# OpenPLC.net
KiCad netlist of a schematic drawn in EAGLE
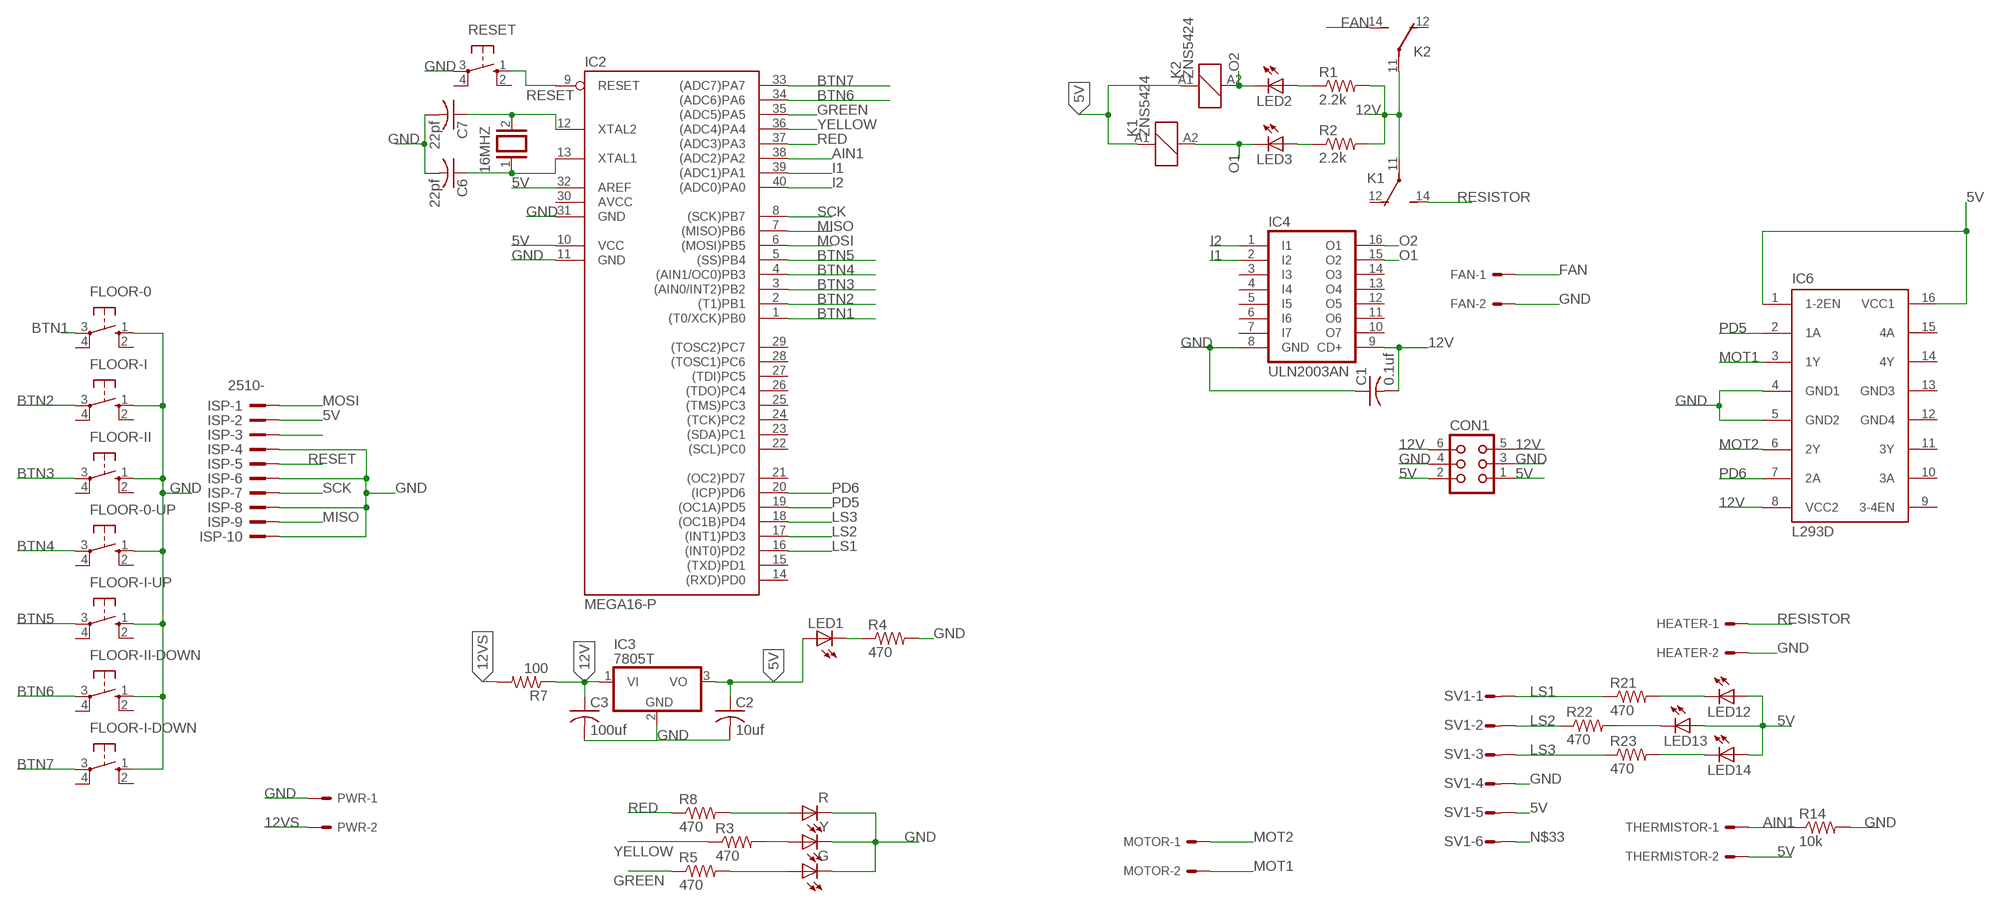
[diagram p0: schematic, sheet 1]

(export (version "E")
  (design (tool "Eeschema 10.0.6"))
  (components
    (comp (ref "16MHZ")
      (value "XTAL/S")
      (footprint "eagle-import:QS")
      (libsource (lib "eagle-import") (part "XTAL/S"))
    )
    (comp (ref "C1")
      (value "0.1uf")
      (footprint "eagle-import:C0805")
      (libsource (lib "eagle-import") (part "C-USC0805"))
    )
    (comp (ref "C2")
      (value "10uf")
      (footprint "eagle-import:C025-025X050")
      (libsource (lib "eagle-import") (part "C-US025-025X050"))
    )
    (comp (ref "C3")
      (value "100uf")
      (footprint "eagle-import:C025-025X050")
      (libsource (lib "eagle-import") (part "C-US025-025X050"))
    )
    (comp (ref "C6")
      (value "22pf")
      (footprint "eagle-import:C0805")
      (libsource (lib "eagle-import") (part "C-USC0805"))
    )
    (comp (ref "C7")
      (value "22pf")
      (footprint "eagle-import:C0805")
      (libsource (lib "eagle-import") (part "C-USC0805"))
    )
    (comp (ref "CON1")
      (value "CON06")
      (footprint "eagle-import:CON06")
      (libsource (lib "eagle-import") (part "CON06"))
    )
    (comp (ref "FAN")
      (value "KK-156-2")
      (footprint "eagle-import:KK-156-2")
      (libsource (lib "eagle-import") (part "KK-156-2"))
    )
    (comp (ref "FLOOR-0")
      (value "10-XX")
      (footprint "eagle-import:B3F-10XX")
      (fields (field (name "MPN") "B3F-1000"))
      (libsource (lib "eagle-import") (part "10-XX"))
    )
    (comp (ref "FLOOR-0-UP")
      (value "10-XX")
      (footprint "eagle-import:B3F-10XX")
      (fields (field (name "MPN") "B3F-1000"))
      (libsource (lib "eagle-import") (part "10-XX"))
    )
    (comp (ref "FLOOR-I")
      (value "10-XX")
      (footprint "eagle-import:B3F-10XX")
      (fields (field (name "MPN") "B3F-1000"))
      (libsource (lib "eagle-import") (part "10-XX"))
    )
    (comp (ref "FLOOR-I-DOWN")
      (value "10-XX")
      (footprint "eagle-import:B3F-10XX")
      (fields (field (name "MPN") "B3F-1000"))
      (libsource (lib "eagle-import") (part "10-XX"))
    )
    (comp (ref "FLOOR-I-UP")
      (value "10-XX")
      (footprint "eagle-import:B3F-10XX")
      (fields (field (name "MPN") "B3F-1000"))
      (libsource (lib "eagle-import") (part "10-XX"))
    )
    (comp (ref "FLOOR-II")
      (value "10-XX")
      (footprint "eagle-import:B3F-10XX")
      (fields (field (name "MPN") "B3F-1000"))
      (libsource (lib "eagle-import") (part "10-XX"))
    )
    (comp (ref "FLOOR-II-DOWN")
      (value "10-XX")
      (footprint "eagle-import:B3F-10XX")
      (fields (field (name "MPN") "B3F-1000"))
      (libsource (lib "eagle-import") (part "10-XX"))
    )
    (comp (ref "G")
      (value "LED10MM")
      (footprint "eagle-import:LED10MM")
      (libsource (lib "eagle-import") (part "LED10MM"))
    )
    (comp (ref "HEATER")
      (value "KK-156-2")
      (footprint "eagle-import:KK-156-2")
      (libsource (lib "eagle-import") (part "KK-156-2"))
    )
    (comp (ref "IC2")
      (value "MEGA16-P")
      (footprint "eagle-import:DIL40")
      (fields (field (name "MPN") "ATMEGA16-16PU"))
      (libsource (lib "eagle-import") (part "MEGA16-P"))
    )
    (comp (ref "IC3")
      (value "7805T")
      (footprint "eagle-import:TO220H")
      (libsource (lib "eagle-import") (part "78T05"))
    )
    (comp (ref "IC4")
      (value "ULN2003AN")
      (footprint "eagle-import:DIL16")
      (libsource (lib "eagle-import") (part "ULN2003AN"))
    )
    (comp (ref "IC6")
      (value "L293D")
      (footprint "eagle-import:DIL16")
      (libsource (lib "eagle-import") (part "L293D"))
    )
    (comp (ref "ISP")
      (value "2510-")
      (footprint "eagle-import:PAK100_2500-10")
      (fields (field (name "MF") "3M") (field (name "MPN") "2510-6002UB"))
      (libsource (lib "eagle-import") (part "2510-"))
    )
    (comp (ref "K1")
      (value "ZNS5424")
      (footprint "eagle-import:ZN5")
      (libsource (lib "eagle-import") (part "ZNS5424"))
    )
    (comp (ref "K2")
      (value "ZNS5424")
      (footprint "eagle-import:ZN5")
      (libsource (lib "eagle-import") (part "ZNS5424"))
    )
    (comp (ref "LED1")
      (value "LEDSML0805")
      (footprint "eagle-import:SML0805")
      (libsource (lib "eagle-import") (part "LEDSML0805"))
    )
    (comp (ref "LED2")
      (value "LEDSML0805")
      (footprint "eagle-import:SML0805")
      (libsource (lib "eagle-import") (part "LEDSML0805"))
    )
    (comp (ref "LED3")
      (value "LEDSML0805")
      (footprint "eagle-import:SML0805")
      (libsource (lib "eagle-import") (part "LEDSML0805"))
    )
    (comp (ref "LED12")
      (value "LEDSML0805")
      (footprint "eagle-import:SML0805")
      (libsource (lib "eagle-import") (part "LEDSML0805"))
    )
    (comp (ref "LED13")
      (value "LEDSML0805")
      (footprint "eagle-import:SML0805")
      (libsource (lib "eagle-import") (part "LEDSML0805"))
    )
    (comp (ref "LED14")
      (value "LEDSML0805")
      (footprint "eagle-import:SML0805")
      (libsource (lib "eagle-import") (part "LEDSML0805"))
    )
    (comp (ref "MOTOR")
      (value "KK-156-2")
      (footprint "eagle-import:KK-156-2")
      (libsource (lib "eagle-import") (part "KK-156-2"))
    )
    (comp (ref "PWR")
      (value "KK-156-2")
      (footprint "eagle-import:KK-156-2")
      (libsource (lib "eagle-import") (part "KK-156-2"))
    )
    (comp (ref "R")
      (value "LED10MM")
      (footprint "eagle-import:LED10MM")
      (libsource (lib "eagle-import") (part "LED10MM"))
    )
    (comp (ref "R1")
      (value "2.2k")
      (footprint "eagle-import:R0805")
      (libsource (lib "eagle-import") (part "R-US_R0805"))
    )
    (comp (ref "R2")
      (value "2.2k")
      (footprint "eagle-import:R0805")
      (libsource (lib "eagle-import") (part "R-US_R0805"))
    )
    (comp (ref "R3")
      (value "470")
      (footprint "eagle-import:R0805")
      (libsource (lib "eagle-import") (part "R-US_R0805"))
    )
    (comp (ref "R4")
      (value "470")
      (footprint "eagle-import:R0805")
      (libsource (lib "eagle-import") (part "R-US_R0805"))
    )
    (comp (ref "R5")
      (value "470")
      (footprint "eagle-import:R0805")
      (libsource (lib "eagle-import") (part "R-US_R0805"))
    )
    (comp (ref "R7")
      (value "100")
      (footprint "eagle-import:0207_12")
      (libsource (lib "eagle-import") (part "R-US_0207/12"))
    )
    (comp (ref "R8")
      (value "470")
      (footprint "eagle-import:R0805")
      (libsource (lib "eagle-import") (part "R-US_R0805"))
    )
    (comp (ref "R14")
      (value "10k")
      (footprint "eagle-import:R0805")
      (libsource (lib "eagle-import") (part "R-US_R0805"))
    )
    (comp (ref "R21")
      (value "470")
      (footprint "eagle-import:R0805")
      (libsource (lib "eagle-import") (part "R-US_R0805"))
    )
    (comp (ref "R22")
      (value "470")
      (footprint "eagle-import:R0805")
      (libsource (lib "eagle-import") (part "R-US_R0805"))
    )
    (comp (ref "R23")
      (value "470")
      (footprint "eagle-import:R0805")
      (libsource (lib "eagle-import") (part "R-US_R0805"))
    )
    (comp (ref "RESET")
      (value "10-XX")
      (footprint "eagle-import:B3F-10XX")
      (fields (field (name "MPN") "B3F-1000"))
      (libsource (lib "eagle-import") (part "10-XX"))
    )
    (comp (ref "SV1")
      (value "L06P")
      (footprint "eagle-import:L06P")
      (libsource (lib "eagle-import") (part "L06P"))
    )
    (comp (ref "THERMISTOR")
      (value "KK-156-2")
      (footprint "eagle-import:KK-156-2")
      (libsource (lib "eagle-import") (part "KK-156-2"))
    )
    (comp (ref "Y")
      (value "LED10MM")
      (footprint "eagle-import:LED10MM")
      (libsource (lib "eagle-import") (part "LED10MM"))
    )
  )
  (nets
    (net (code "1") (name "/AIN1") (class "Default")
      (node (ref "IC2") (pin "38") (pinfunction "(ADC2)PA2_38") (pintype "bidirectional"))
      (node (ref "R14") (pin "1") (pinfunction "1_1") (pintype "passive"))
      (node (ref "THERMISTOR") (pin "1") (pinfunction "S_1") (pintype "passive"))
    )
    (net (code "2") (name "/AVCC") (class "Default")
      (node (ref "IC2") (pin "30") (pinfunction "AVCC_30") (pintype "power_in"))
    )
    (net (code "3") (name "/BTN1") (class "Default")
      (node (ref "FLOOR-0") (pin "3") (pinfunction "P_3") (pintype "passive"))
      (node (ref "IC2") (pin "1") (pinfunction "(T0/XCK)PB0_1") (pintype "bidirectional"))
    )
    (net (code "4") (name "/BTN2") (class "Default")
      (node (ref "FLOOR-I") (pin "3") (pinfunction "P_3") (pintype "passive"))
      (node (ref "IC2") (pin "2") (pinfunction "(T1)PB1_2") (pintype "bidirectional"))
    )
    (net (code "5") (name "/BTN3") (class "Default")
      (node (ref "FLOOR-II") (pin "3") (pinfunction "P_3") (pintype "passive"))
      (node (ref "IC2") (pin "3") (pinfunction "(AIN0/INT2)PB2_3") (pintype "bidirectional"))
    )
    (net (code "6") (name "/BTN4") (class "Default")
      (node (ref "FLOOR-0-UP") (pin "3") (pinfunction "P_3") (pintype "passive"))
      (node (ref "IC2") (pin "4") (pinfunction "(AIN1/OC0)PB3_4") (pintype "bidirectional"))
    )
    (net (code "7") (name "/BTN5") (class "Default")
      (node (ref "FLOOR-I-UP") (pin "3") (pinfunction "P_3") (pintype "passive"))
      (node (ref "IC2") (pin "5") (pinfunction "(SS)PB4_5") (pintype "bidirectional"))
    )
    (net (code "8") (name "/BTN6") (class "Default")
      (node (ref "FLOOR-II-DOWN") (pin "3") (pinfunction "P_3") (pintype "passive"))
      (node (ref "IC2") (pin "34") (pinfunction "(ADC6)PA6_34") (pintype "bidirectional"))
    )
    (net (code "9") (name "/BTN7") (class "Default")
      (node (ref "FLOOR-I-DOWN") (pin "3") (pinfunction "P_3") (pintype "passive"))
      (node (ref "IC2") (pin "33") (pinfunction "(ADC7)PA7_33") (pintype "bidirectional"))
    )
    (net (code "10") (name "/FAN") (class "Default")
      (node (ref "FAN") (pin "1") (pinfunction "S_1") (pintype "passive"))
      (node (ref "K2") (pin "14") (pinfunction "S_14") (pintype "passive"))
    )
    (net (code "11") (name "/GND") (class "Default")
      (node (ref "C1") (pin "1") (pinfunction "1_1") (pintype "passive"))
      (node (ref "C2") (pin "2") (pinfunction "2_2") (pintype "passive"))
      (node (ref "C3") (pin "2") (pinfunction "2_2") (pintype "passive"))
      (node (ref "C6") (pin "2") (pinfunction "2_2") (pintype "passive"))
      (node (ref "C7") (pin "2") (pinfunction "2_2") (pintype "passive"))
      (node (ref "CON1") (pin "3") (pinfunction "3_3") (pintype "passive"))
      (node (ref "CON1") (pin "4") (pinfunction "4_4") (pintype "passive"))
      (node (ref "FAN") (pin "2") (pinfunction "S_2") (pintype "passive"))
      (node (ref "FLOOR-0") (pin "1") (pinfunction "S_1") (pintype "passive"))
      (node (ref "FLOOR-0-UP") (pin "1") (pinfunction "S_1") (pintype "passive"))
      (node (ref "FLOOR-I") (pin "1") (pinfunction "S_1") (pintype "passive"))
      (node (ref "FLOOR-I-DOWN") (pin "1") (pinfunction "S_1") (pintype "passive"))
      (node (ref "FLOOR-I-UP") (pin "1") (pinfunction "S_1") (pintype "passive"))
      (node (ref "FLOOR-II") (pin "1") (pinfunction "S_1") (pintype "passive"))
      (node (ref "FLOOR-II-DOWN") (pin "1") (pinfunction "S_1") (pintype "passive"))
      (node (ref "G") (pin "K") (pinfunction "C_K") (pintype "passive"))
      (node (ref "HEATER") (pin "2") (pinfunction "S_2") (pintype "passive"))
      (node (ref "IC2") (pin "11") (pinfunction "GND_11") (pintype "power_in"))
      (node (ref "IC2") (pin "31") (pinfunction "GND_31") (pintype "power_in"))
      (node (ref "IC3") (pin "2") (pinfunction "GND_2") (pintype "passive"))
      (node (ref "IC4") (pin "8") (pinfunction "GND_8") (pintype "power_in"))
      (node (ref "IC6") (pin "4") (pinfunction "GND1_4") (pintype "power_in"))
      (node (ref "IC6") (pin "5") (pinfunction "GND2_5") (pintype "power_in"))
      (node (ref "ISP") (pin "10") (pinfunction "KL_10") (pintype "passive"))
      (node (ref "ISP") (pin "4") (pinfunction "KL_4") (pintype "passive"))
      (node (ref "ISP") (pin "6") (pinfunction "KL_6") (pintype "passive"))
      (node (ref "ISP") (pin "8") (pinfunction "KL_8") (pintype "passive"))
      (node (ref "PWR") (pin "1") (pinfunction "S_1") (pintype "passive"))
      (node (ref "R") (pin "K") (pinfunction "C_K") (pintype "passive"))
      (node (ref "R14") (pin "2") (pinfunction "2_2") (pintype "passive"))
      (node (ref "R4") (pin "2") (pinfunction "2_2") (pintype "passive"))
      (node (ref "RESET") (pin "3") (pinfunction "P_3") (pintype "passive"))
      (node (ref "SV1") (pin "4") (pinfunction "S_4") (pintype "passive"))
      (node (ref "Y") (pin "K") (pinfunction "C_K") (pintype "passive"))
    )
    (net (code "12") (name "/GND3") (class "Default")
      (node (ref "IC6") (pin "13") (pinfunction "GND3_13") (pintype "power_in"))
    )
    (net (code "13") (name "/GND4") (class "Default")
      (node (ref "IC6") (pin "12") (pinfunction "GND4_12") (pintype "power_in"))
    )
    (net (code "14") (name "/GREEN") (class "Default")
      (node (ref "IC2") (pin "35") (pinfunction "(ADC5)PA5_35") (pintype "bidirectional"))
      (node (ref "R5") (pin "1") (pinfunction "1_1") (pintype "passive"))
    )
    (net (code "15") (name "/I1") (class "Default")
      (node (ref "IC2") (pin "39") (pinfunction "(ADC1)PA1_39") (pintype "bidirectional"))
      (node (ref "IC4") (pin "2") (pinfunction "I2_2") (pintype "input"))
    )
    (net (code "16") (name "/I2") (class "Default")
      (node (ref "IC2") (pin "40") (pinfunction "(ADC0)PA0_40") (pintype "bidirectional"))
      (node (ref "IC4") (pin "1") (pinfunction "I1_1") (pintype "input"))
    )
    (net (code "17") (name "/LS1") (class "Default")
      (node (ref "IC2") (pin "16") (pinfunction "(INT0)PD2_16") (pintype "bidirectional"))
      (node (ref "R21") (pin "1") (pinfunction "1_1") (pintype "passive"))
      (node (ref "SV1") (pin "1") (pinfunction "S_1") (pintype "passive"))
    )
    (net (code "18") (name "/LS2") (class "Default")
      (node (ref "IC2") (pin "17") (pinfunction "(INT1)PD3_17") (pintype "bidirectional"))
      (node (ref "R22") (pin "1") (pinfunction "1_1") (pintype "passive"))
      (node (ref "SV1") (pin "2") (pinfunction "S_2") (pintype "passive"))
    )
    (net (code "19") (name "/LS3") (class "Default")
      (node (ref "IC2") (pin "18") (pinfunction "(OC1B)PD4_18") (pintype "bidirectional"))
      (node (ref "R23") (pin "1") (pinfunction "1_1") (pintype "passive"))
      (node (ref "SV1") (pin "3") (pinfunction "S_3") (pintype "passive"))
    )
    (net (code "20") (name "/MISO") (class "Default")
      (node (ref "IC2") (pin "7") (pinfunction "(MISO)PB6_7") (pintype "bidirectional"))
      (node (ref "ISP") (pin "9") (pinfunction "KL_9") (pintype "passive"))
    )
    (net (code "21") (name "/MOSI") (class "Default")
      (node (ref "IC2") (pin "6") (pinfunction "(MOSI)PB5_6") (pintype "bidirectional"))
      (node (ref "ISP") (pin "1") (pinfunction "KL_1") (pintype "passive"))
    )
    (net (code "22") (name "/MOT1") (class "Default")
      (node (ref "IC6") (pin "3") (pinfunction "1Y_3") (pintype "output"))
      (node (ref "MOTOR") (pin "2") (pinfunction "S_2") (pintype "passive"))
    )
    (net (code "23") (name "/MOT2") (class "Default")
      (node (ref "IC6") (pin "6") (pinfunction "2Y_6") (pintype "output"))
      (node (ref "MOTOR") (pin "1") (pinfunction "S_1") (pintype "passive"))
    )
    (net (code "24") (name "/N$33") (class "Default")
      (node (ref "SV1") (pin "6") (pinfunction "S_6") (pintype "passive"))
    )
    (net (code "25") (name "/O1") (class "Default")
      (node (ref "IC4") (pin "15") (pinfunction "O2_15") (pintype "open_collector"))
      (node (ref "K1") (pin "A2") (pinfunction "2_A2") (pintype "passive"))
      (node (ref "LED3") (pin "C") (pinfunction "C_C") (pintype "passive"))
    )
    (net (code "26") (name "/O2") (class "Default")
      (node (ref "IC4") (pin "16") (pinfunction "O1_16") (pintype "open_collector"))
      (node (ref "K2") (pin "A2") (pinfunction "2_A2") (pintype "passive"))
      (node (ref "LED2") (pin "C") (pinfunction "C_C") (pintype "passive"))
    )
    (net (code "27") (name "/PD5") (class "Default")
      (node (ref "IC2") (pin "19") (pinfunction "(OC1A)PD5_19") (pintype "bidirectional"))
      (node (ref "IC6") (pin "2") (pinfunction "1A_2") (pintype "input"))
    )
    (net (code "28") (name "/PD6") (class "Default")
      (node (ref "IC2") (pin "20") (pinfunction "(ICP)PD6_20") (pintype "bidirectional"))
      (node (ref "IC6") (pin "7") (pinfunction "2A_7") (pintype "input"))
    )
    (net (code "29") (name "/RED") (class "Default")
      (node (ref "IC2") (pin "37") (pinfunction "(ADC3)PA3_37") (pintype "bidirectional"))
      (node (ref "R8") (pin "1") (pinfunction "1_1") (pintype "passive"))
    )
    (net (code "30") (name "/RESET") (class "Default")
      (node (ref "IC2") (pin "9") (pinfunction "RESET_9") (pintype "input"))
      (node (ref "ISP") (pin "5") (pinfunction "KL_5") (pintype "passive"))
      (node (ref "RESET") (pin "1") (pinfunction "S_1") (pintype "passive"))
    )
    (net (code "31") (name "/RESISTOR") (class "Default")
      (node (ref "HEATER") (pin "1") (pinfunction "S_1") (pintype "passive"))
      (node (ref "K1") (pin "14") (pinfunction "S_14") (pintype "passive"))
    )
    (net (code "32") (name "/SCK") (class "Default")
      (node (ref "IC2") (pin "8") (pinfunction "(SCK)PB7_8") (pintype "bidirectional"))
      (node (ref "ISP") (pin "7") (pinfunction "KL_7") (pintype "passive"))
    )
    (net (code "33") (name "/YELLOW") (class "Default")
      (node (ref "IC2") (pin "36") (pinfunction "(ADC4)PA4_36") (pintype "bidirectional"))
      (node (ref "R3") (pin "1") (pinfunction "1_1") (pintype "passive"))
    )
    (net (code "34") (name "5V") (class "Default")
      (node (ref "C2") (pin "1") (pinfunction "1_1") (pintype "passive"))
      (node (ref "CON1") (pin "1") (pinfunction "1_1") (pintype "passive"))
      (node (ref "CON1") (pin "2") (pinfunction "2_2") (pintype "passive"))
      (node (ref "IC2") (pin "10") (pinfunction "VCC_10") (pintype "power_in"))
      (node (ref "IC2") (pin "32") (pinfunction "AREF_32") (pintype "passive"))
      (node (ref "IC3") (pin "3") (pinfunction "VO_3") (pintype "passive"))
      (node (ref "IC6") (pin "1") (pinfunction "1-2EN_1") (pintype "input"))
      (node (ref "IC6") (pin "16") (pinfunction "VCC1_16") (pintype "power_in"))
      (node (ref "ISP") (pin "2") (pinfunction "KL_2") (pintype "passive"))
      (node (ref "K1") (pin "A1") (pinfunction "1_A1") (pintype "passive"))
      (node (ref "K2") (pin "A1") (pinfunction "1_A1") (pintype "passive"))
      (node (ref "LED1") (pin "A") (pinfunction "A_A") (pintype "passive"))
      (node (ref "LED12") (pin "A") (pinfunction "A_A") (pintype "passive"))
      (node (ref "LED13") (pin "A") (pinfunction "A_A") (pintype "passive"))
      (node (ref "LED14") (pin "A") (pinfunction "A_A") (pintype "passive"))
      (node (ref "SV1") (pin "5") (pinfunction "S_5") (pintype "passive"))
      (node (ref "THERMISTOR") (pin "2") (pinfunction "S_2") (pintype "passive"))
    )
    (net (code "35") (name "12V") (class "Default")
      (node (ref "C1") (pin "2") (pinfunction "2_2") (pintype "passive"))
      (node (ref "C3") (pin "1") (pinfunction "1_1") (pintype "passive"))
      (node (ref "CON1") (pin "5") (pinfunction "5_5") (pintype "passive"))
      (node (ref "CON1") (pin "6") (pinfunction "6_6") (pintype "passive"))
      (node (ref "IC3") (pin "1") (pinfunction "VI_1") (pintype "input"))
      (node (ref "IC4") (pin "9") (pinfunction "CD+_9") (pintype "passive"))
      (node (ref "IC6") (pin "8") (pinfunction "VCC2_8") (pintype "power_in"))
      (node (ref "K1") (pin "11") (pinfunction "P_11") (pintype "passive"))
      (node (ref "K2") (pin "11") (pinfunction "P_11") (pintype "passive"))
      (node (ref "R1") (pin "2") (pinfunction "2_2") (pintype "passive"))
      (node (ref "R2") (pin "2") (pinfunction "2_2") (pintype "passive"))
      (node (ref "R7") (pin "1") (pinfunction "1_1") (pintype "passive"))
    )
    (net (code "36") (name "12VS") (class "Default")
      (node (ref "PWR") (pin "2") (pinfunction "S_2") (pintype "passive"))
      (node (ref "R7") (pin "2") (pinfunction "2_2") (pintype "passive"))
    )
    (net (code "37") (name "Net-(G-PadA)") (class "Default")
      (node (ref "G") (pin "A") (pinfunction "A_A") (pintype "passive"))
      (node (ref "R5") (pin "2") (pinfunction "2_2") (pintype "passive"))
    )
    (net (code "38") (name "Net-(IC2-XTAL1)") (class "Default")
      (node (ref "16MHZ") (pin "1") (pinfunction "1_1") (pintype "passive"))
      (node (ref "C6") (pin "1") (pinfunction "1_1") (pintype "passive"))
      (node (ref "IC2") (pin "13") (pinfunction "XTAL1_13") (pintype "bidirectional"))
    )
    (net (code "39") (name "Net-(IC2-XTAL2)") (class "Default")
      (node (ref "16MHZ") (pin "2") (pinfunction "2_2") (pintype "passive"))
      (node (ref "C7") (pin "1") (pinfunction "1_1") (pintype "passive"))
      (node (ref "IC2") (pin "12") (pinfunction "XTAL2_12") (pintype "bidirectional"))
    )
    (net (code "40") (name "Net-(LED1-PadC)") (class "Default")
      (node (ref "LED1") (pin "C") (pinfunction "C_C") (pintype "passive"))
      (node (ref "R4") (pin "1") (pinfunction "1_1") (pintype "passive"))
    )
    (net (code "41") (name "Net-(LED2-PadA)") (class "Default")
      (node (ref "LED2") (pin "A") (pinfunction "A_A") (pintype "passive"))
      (node (ref "R1") (pin "1") (pinfunction "1_1") (pintype "passive"))
    )
    (net (code "42") (name "Net-(LED3-PadA)") (class "Default")
      (node (ref "LED3") (pin "A") (pinfunction "A_A") (pintype "passive"))
      (node (ref "R2") (pin "1") (pinfunction "1_1") (pintype "passive"))
    )
    (net (code "43") (name "Net-(LED12-PadC)") (class "Default")
      (node (ref "LED12") (pin "C") (pinfunction "C_C") (pintype "passive"))
      (node (ref "R21") (pin "2") (pinfunction "2_2") (pintype "passive"))
    )
    (net (code "44") (name "Net-(LED13-PadC)") (class "Default")
      (node (ref "LED13") (pin "C") (pinfunction "C_C") (pintype "passive"))
      (node (ref "R22") (pin "2") (pinfunction "2_2") (pintype "passive"))
    )
    (net (code "45") (name "Net-(LED14-PadC)") (class "Default")
      (node (ref "LED14") (pin "C") (pinfunction "C_C") (pintype "passive"))
      (node (ref "R23") (pin "2") (pinfunction "2_2") (pintype "passive"))
    )
    (net (code "46") (name "Net-(R-PadA)") (class "Default")
      (node (ref "R") (pin "A") (pinfunction "A_A") (pintype "passive"))
      (node (ref "R8") (pin "2") (pinfunction "2_2") (pintype "passive"))
    )
    (net (code "47") (name "Net-(R3-Pad2)") (class "Default")
      (node (ref "R3") (pin "2") (pinfunction "2_2") (pintype "passive"))
      (node (ref "Y") (pin "A") (pinfunction "A_A") (pintype "passive"))
    )
    (net (code "48") (name "unconnected-(FLOOR-0-P1-Pad4)") (class "Default")
      (node (ref "FLOOR-0") (pin "4") (pinfunction "P1_4") (pintype "passive"))
    )
    (net (code "49") (name "unconnected-(FLOOR-0-S1-Pad2)") (class "Default")
      (node (ref "FLOOR-0") (pin "2") (pinfunction "S1_2") (pintype "passive"))
    )
    (net (code "50") (name "unconnected-(FLOOR-0-UP-P1-Pad4)") (class "Default")
      (node (ref "FLOOR-0-UP") (pin "4") (pinfunction "P1_4") (pintype "passive"))
    )
    (net (code "51") (name "unconnected-(FLOOR-0-UP-S1-Pad2)") (class "Default")
      (node (ref "FLOOR-0-UP") (pin "2") (pinfunction "S1_2") (pintype "passive"))
    )
    (net (code "52") (name "unconnected-(FLOOR-I-DOWN-P1-Pad4)") (class "Default")
      (node (ref "FLOOR-I-DOWN") (pin "4") (pinfunction "P1_4") (pintype "passive"))
    )
    (net (code "53") (name "unconnected-(FLOOR-I-DOWN-S1-Pad2)") (class "Default")
      (node (ref "FLOOR-I-DOWN") (pin "2") (pinfunction "S1_2") (pintype "passive"))
    )
    (net (code "54") (name "unconnected-(FLOOR-I-P1-Pad4)") (class "Default")
      (node (ref "FLOOR-I") (pin "4") (pinfunction "P1_4") (pintype "passive"))
    )
    (net (code "55") (name "unconnected-(FLOOR-I-S1-Pad2)") (class "Default")
      (node (ref "FLOOR-I") (pin "2") (pinfunction "S1_2") (pintype "passive"))
    )
    (net (code "56") (name "unconnected-(FLOOR-I-UP-P1-Pad4)") (class "Default")
      (node (ref "FLOOR-I-UP") (pin "4") (pinfunction "P1_4") (pintype "passive"))
    )
    (net (code "57") (name "unconnected-(FLOOR-I-UP-S1-Pad2)") (class "Default")
      (node (ref "FLOOR-I-UP") (pin "2") (pinfunction "S1_2") (pintype "passive"))
    )
    (net (code "58") (name "unconnected-(FLOOR-II-DOWN-P1-Pad4)") (class "Default")
      (node (ref "FLOOR-II-DOWN") (pin "4") (pinfunction "P1_4") (pintype "passive"))
    )
    (net (code "59") (name "unconnected-(FLOOR-II-DOWN-S1-Pad2)") (class "Default")
      (node (ref "FLOOR-II-DOWN") (pin "2") (pinfunction "S1_2") (pintype "passive"))
    )
    (net (code "60") (name "unconnected-(FLOOR-II-P1-Pad4)") (class "Default")
      (node (ref "FLOOR-II") (pin "4") (pinfunction "P1_4") (pintype "passive"))
    )
    (net (code "61") (name "unconnected-(FLOOR-II-S1-Pad2)") (class "Default")
      (node (ref "FLOOR-II") (pin "2") (pinfunction "S1_2") (pintype "passive"))
    )
    (net (code "62") (name "unconnected-(IC2-(OC2)PD7-Pad21)") (class "Default")
      (node (ref "IC2") (pin "21") (pinfunction "(OC2)PD7_21") (pintype "bidirectional"))
    )
    (net (code "63") (name "unconnected-(IC2-(RXD)PD0-Pad14)") (class "Default")
      (node (ref "IC2") (pin "14") (pinfunction "(RXD)PD0_14") (pintype "bidirectional"))
    )
    (net (code "64") (name "unconnected-(IC2-(SCL)PC0-Pad22)") (class "Default")
      (node (ref "IC2") (pin "22") (pinfunction "(SCL)PC0_22") (pintype "bidirectional"))
    )
    (net (code "65") (name "unconnected-(IC2-(SDA)PC1-Pad23)") (class "Default")
      (node (ref "IC2") (pin "23") (pinfunction "(SDA)PC1_23") (pintype "bidirectional"))
    )
    (net (code "66") (name "unconnected-(IC2-(TCK)PC2-Pad24)") (class "Default")
      (node (ref "IC2") (pin "24") (pinfunction "(TCK)PC2_24") (pintype "bidirectional"))
    )
    (net (code "67") (name "unconnected-(IC2-(TDI)PC5-Pad27)") (class "Default")
      (node (ref "IC2") (pin "27") (pinfunction "(TDI)PC5_27") (pintype "bidirectional"))
    )
    (net (code "68") (name "unconnected-(IC2-(TDO)PC4-Pad26)") (class "Default")
      (node (ref "IC2") (pin "26") (pinfunction "(TDO)PC4_26") (pintype "bidirectional"))
    )
    (net (code "69") (name "unconnected-(IC2-(TMS)PC3-Pad25)") (class "Default")
      (node (ref "IC2") (pin "25") (pinfunction "(TMS)PC3_25") (pintype "bidirectional"))
    )
    (net (code "70") (name "unconnected-(IC2-(TOSC1)PC6-Pad28)") (class "Default")
      (node (ref "IC2") (pin "28") (pinfunction "(TOSC1)PC6_28") (pintype "bidirectional"))
    )
    (net (code "71") (name "unconnected-(IC2-(TOSC2)PC7-Pad29)") (class "Default")
      (node (ref "IC2") (pin "29") (pinfunction "(TOSC2)PC7_29") (pintype "bidirectional"))
    )
    (net (code "72") (name "unconnected-(IC2-(TXD)PD1-Pad15)") (class "Default")
      (node (ref "IC2") (pin "15") (pinfunction "(TXD)PD1_15") (pintype "bidirectional"))
    )
    (net (code "73") (name "unconnected-(IC4-I3-Pad3)") (class "Default")
      (node (ref "IC4") (pin "3") (pinfunction "I3_3") (pintype "input"))
    )
    (net (code "74") (name "unconnected-(IC4-I4-Pad4)") (class "Default")
      (node (ref "IC4") (pin "4") (pinfunction "I4_4") (pintype "input"))
    )
    (net (code "75") (name "unconnected-(IC4-I5-Pad5)") (class "Default")
      (node (ref "IC4") (pin "5") (pinfunction "I5_5") (pintype "input"))
    )
    (net (code "76") (name "unconnected-(IC4-I6-Pad6)") (class "Default")
      (node (ref "IC4") (pin "6") (pinfunction "I6_6") (pintype "input"))
    )
    (net (code "77") (name "unconnected-(IC4-I7-Pad7)") (class "Default")
      (node (ref "IC4") (pin "7") (pinfunction "I7_7") (pintype "input"))
    )
    (net (code "78") (name "unconnected-(IC4-O3-Pad14)") (class "Default")
      (node (ref "IC4") (pin "14") (pinfunction "O3_14") (pintype "open_collector"))
    )
    (net (code "79") (name "unconnected-(IC4-O4-Pad13)") (class "Default")
      (node (ref "IC4") (pin "13") (pinfunction "O4_13") (pintype "open_collector"))
    )
    (net (code "80") (name "unconnected-(IC4-O5-Pad12)") (class "Default")
      (node (ref "IC4") (pin "12") (pinfunction "O5_12") (pintype "open_collector"))
    )
    (net (code "81") (name "unconnected-(IC4-O6-Pad11)") (class "Default")
      (node (ref "IC4") (pin "11") (pinfunction "O6_11") (pintype "open_collector"))
    )
    (net (code "82") (name "unconnected-(IC4-O7-Pad10)") (class "Default")
      (node (ref "IC4") (pin "10") (pinfunction "O7_10") (pintype "open_collector"))
    )
    (net (code "83") (name "unconnected-(IC6-3-4EN-Pad9)") (class "Default")
      (node (ref "IC6") (pin "9") (pinfunction "3-4EN_9") (pintype "input"))
    )
    (net (code "84") (name "unconnected-(IC6-3A-Pad10)") (class "Default")
      (node (ref "IC6") (pin "10") (pinfunction "3A_10") (pintype "input"))
    )
    (net (code "85") (name "unconnected-(IC6-3Y-Pad11)") (class "Default")
      (node (ref "IC6") (pin "11") (pinfunction "3Y_11") (pintype "output"))
    )
    (net (code "86") (name "unconnected-(IC6-4A-Pad15)") (class "Default")
      (node (ref "IC6") (pin "15") (pinfunction "4A_15") (pintype "input"))
    )
    (net (code "87") (name "unconnected-(IC6-4Y-Pad14)") (class "Default")
      (node (ref "IC6") (pin "14") (pinfunction "4Y_14") (pintype "output"))
    )
    (net (code "88") (name "unconnected-(ISPD-KL-Pad3)") (class "Default")
      (node (ref "ISP") (pin "3") (pinfunction "KL_3") (pintype "passive"))
    )
    (net (code "89") (name "unconnected-(K1B-O-Pad12)") (class "Default")
      (node (ref "K1") (pin "12") (pinfunction "O_12") (pintype "passive"))
    )
    (net (code "90") (name "unconnected-(K2B-O-Pad12)") (class "Default")
      (node (ref "K2") (pin "12") (pinfunction "O_12") (pintype "passive"))
    )
    (net (code "91") (name "unconnected-(RESET-P1-Pad4)") (class "Default")
      (node (ref "RESET") (pin "4") (pinfunction "P1_4") (pintype "passive"))
    )
    (net (code "92") (name "unconnected-(RESET-S1-Pad2)") (class "Default")
      (node (ref "RESET") (pin "2") (pinfunction "S1_2") (pintype "passive"))
    )
  )
)
